# ESP32_SimButtonBox_Controller.net
KiCad netlist of a schematic drawn in EAGLE
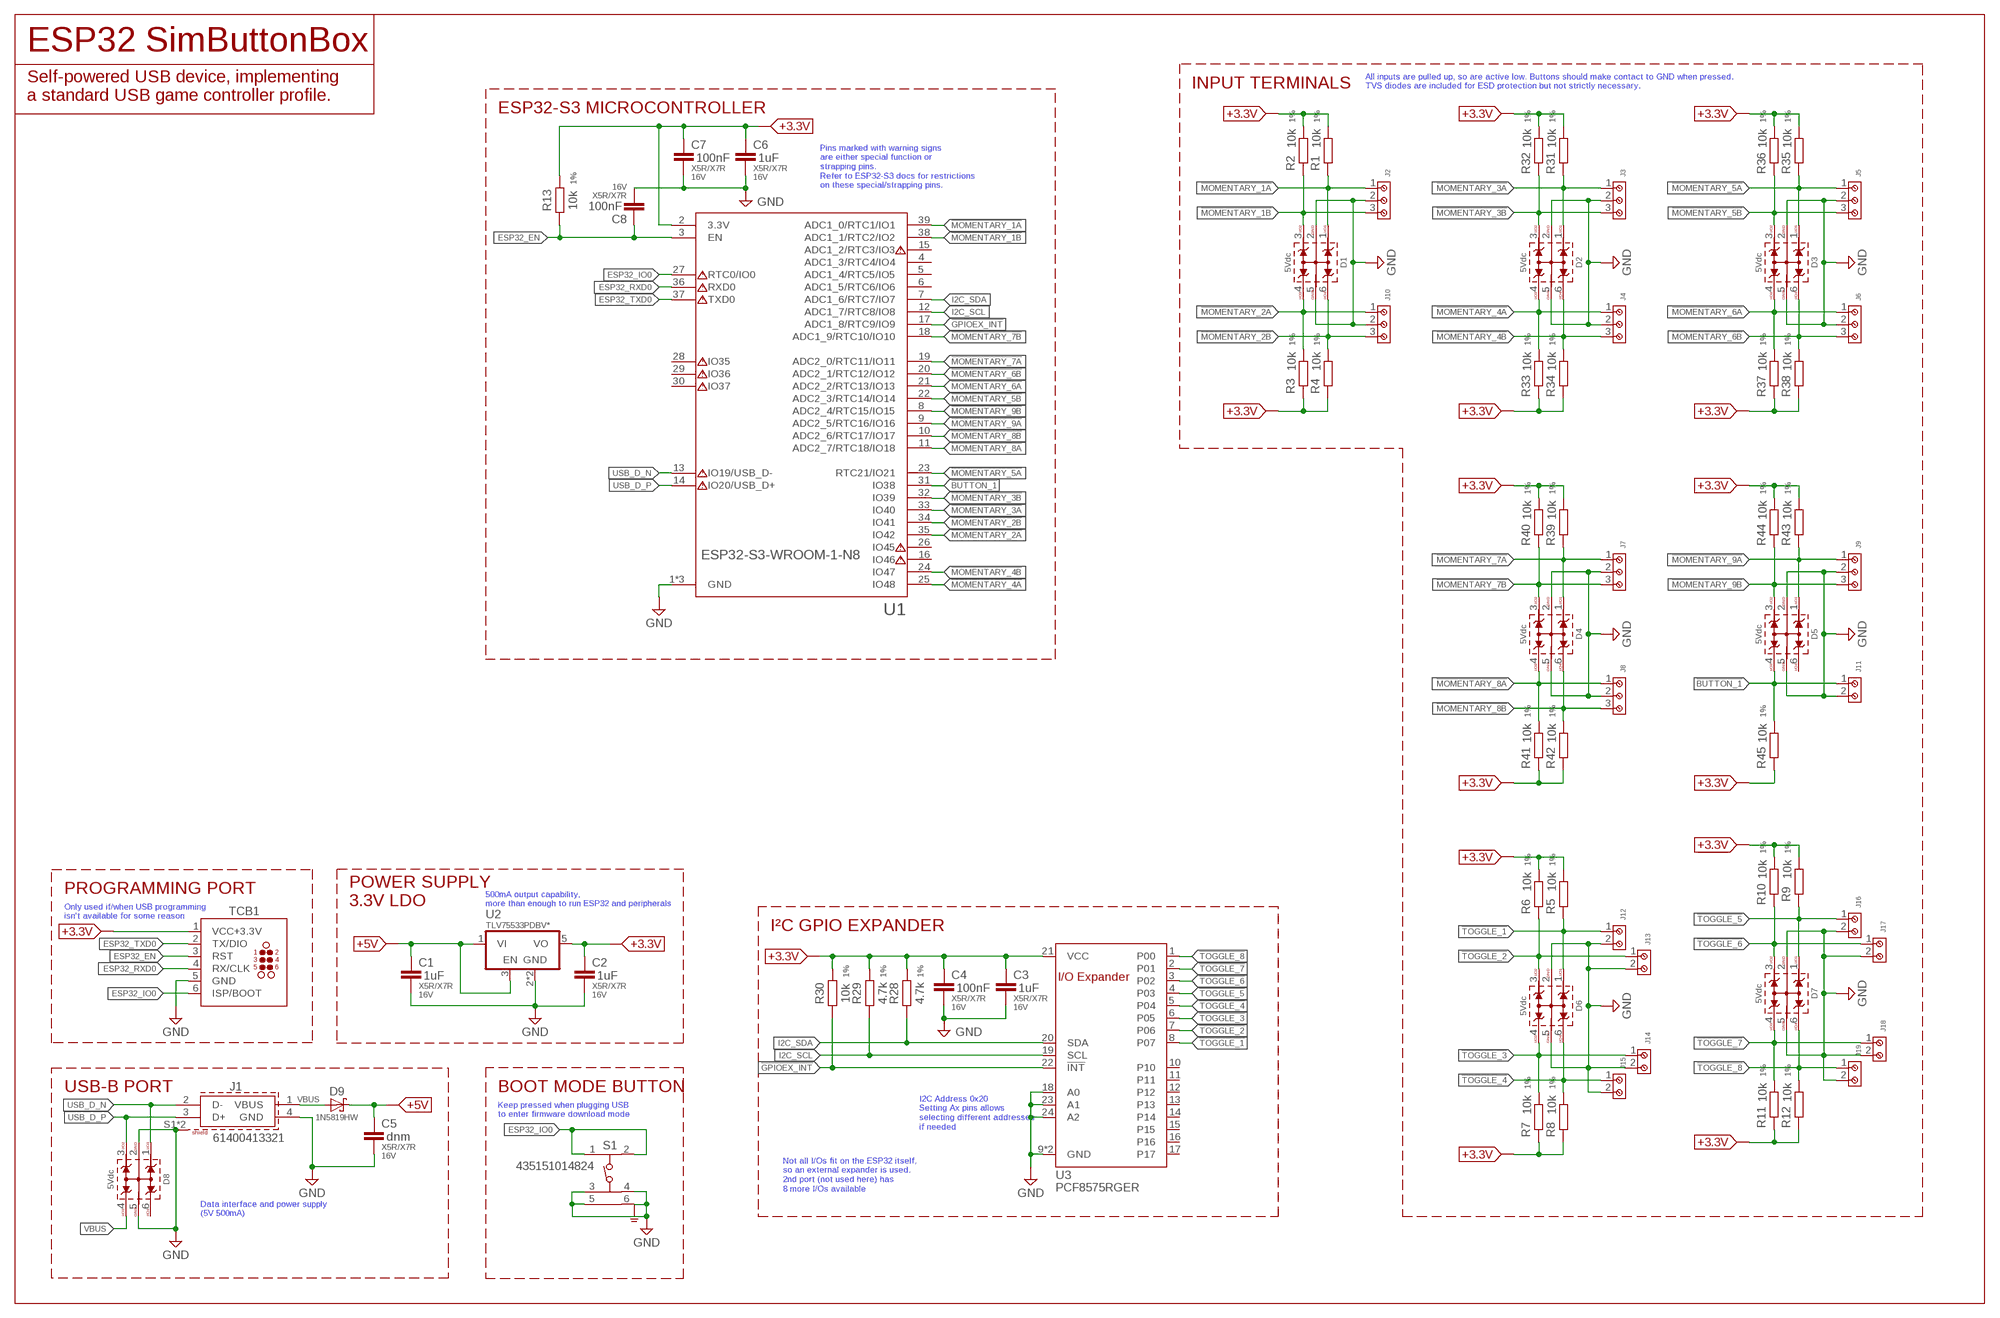
[diagram p0: schematic, sheet 1]

(export (version "E")
  (design (tool "Eeschema 10.0.6"))
  (components
    (comp (ref "C1")
      (value "1uF")
      (footprint "eagle-import:C0603")
      (fields (field (name "MATERIAL") "X5R/X7R") (field (name "VOLTAGE") "16V"))
      (libsource (lib "eagle-import") (part "CAP_0603"))
    )
    (comp (ref "C2")
      (value "1uF")
      (footprint "eagle-import:C0603")
      (fields (field (name "MATERIAL") "X5R/X7R") (field (name "VOLTAGE") "16V"))
      (libsource (lib "eagle-import") (part "CAP_0603"))
    )
    (comp (ref "C3")
      (value "1uF")
      (footprint "eagle-import:C0603")
      (fields (field (name "MATERIAL") "X5R/X7R") (field (name "VOLTAGE") "16V"))
      (libsource (lib "eagle-import") (part "CAP_0603"))
    )
    (comp (ref "C4")
      (value "100nF")
      (footprint "eagle-import:C0603")
      (fields (field (name "MATERIAL") "X5R/X7R") (field (name "VOLTAGE") "16V"))
      (libsource (lib "eagle-import") (part "CAP_0603"))
    )
    (comp (ref "C5")
      (value "dnm")
      (footprint "eagle-import:C0603")
      (fields (field (name "MATERIAL") "X5R/X7R") (field (name "VOLTAGE") "16V"))
      (libsource (lib "eagle-import") (part "CAP_0603"))
    )
    (comp (ref "C6")
      (value "1uF")
      (footprint "eagle-import:C0603")
      (fields (field (name "MATERIAL") "X5R/X7R") (field (name "VOLTAGE") "16V"))
      (libsource (lib "eagle-import") (part "CAP_0603"))
    )
    (comp (ref "C7")
      (value "100nF")
      (footprint "eagle-import:C0603")
      (fields (field (name "MATERIAL") "X5R/X7R") (field (name "VOLTAGE") "16V"))
      (libsource (lib "eagle-import") (part "CAP_0603"))
    )
    (comp (ref "C8")
      (value "100nF")
      (footprint "eagle-import:C0603")
      (fields (field (name "MATERIAL") "X5R/X7R") (field (name "VOLTAGE") "16V"))
      (libsource (lib "eagle-import") (part "CAP_0603"))
    )
    (comp (ref "D1")
      (value "5Vdc")
      (footprint "eagle-import:WE-TVS_SOT23-6L")
      (fields (field (name "MF") "Wurth Elektronik") (field (name "MP") "82402304"))
      (libsource (lib "eagle-import") (part "WE-TVS_SOT23-6L_82402304"))
    )
    (comp (ref "D2")
      (value "5Vdc")
      (footprint "eagle-import:WE-TVS_SOT23-6L")
      (fields (field (name "MF") "Wurth Elektronik") (field (name "MP") "82402304"))
      (libsource (lib "eagle-import") (part "WE-TVS_SOT23-6L_82402304"))
    )
    (comp (ref "D3")
      (value "5Vdc")
      (footprint "eagle-import:WE-TVS_SOT23-6L")
      (fields (field (name "MF") "Wurth Elektronik") (field (name "MP") "82402304"))
      (libsource (lib "eagle-import") (part "WE-TVS_SOT23-6L_82402304"))
    )
    (comp (ref "D4")
      (value "5Vdc")
      (footprint "eagle-import:WE-TVS_SOT23-6L")
      (fields (field (name "MF") "Wurth Elektronik") (field (name "MP") "82402304"))
      (libsource (lib "eagle-import") (part "WE-TVS_SOT23-6L_82402304"))
    )
    (comp (ref "D5")
      (value "5Vdc")
      (footprint "eagle-import:WE-TVS_SOT23-6L")
      (fields (field (name "MF") "Wurth Elektronik") (field (name "MP") "82402304"))
      (libsource (lib "eagle-import") (part "WE-TVS_SOT23-6L_82402304"))
    )
    (comp (ref "D6")
      (value "5Vdc")
      (footprint "eagle-import:WE-TVS_SOT23-6L")
      (fields (field (name "MF") "Wurth Elektronik") (field (name "MP") "82402304"))
      (libsource (lib "eagle-import") (part "WE-TVS_SOT23-6L_82402304"))
    )
    (comp (ref "D7")
      (value "5Vdc")
      (footprint "eagle-import:WE-TVS_SOT23-6L")
      (fields (field (name "MF") "Wurth Elektronik") (field (name "MP") "82402304"))
      (libsource (lib "eagle-import") (part "WE-TVS_SOT23-6L_82402304"))
    )
    (comp (ref "D8")
      (value "5Vdc")
      (footprint "eagle-import:WE-TVS_SOT23-6L")
      (fields (field (name "MF") "Wurth Elektronik") (field (name "MP") "82402304"))
      (libsource (lib "eagle-import") (part "WE-TVS_SOT23-6L_82402304"))
    )
    (comp (ref "D9")
      (value "1N5819HW")
      (footprint "eagle-import:SOD123")
      (fields (field (name "CURRENT") "1A") (field (name "MP") "1N5819HW"))
      (libsource (lib "eagle-import") (part "SCHOTTKY_SOD123"))
    )
    (comp (ref "J1")
      (value "61400413321")
      (footprint "eagle-import:61400413321")
      (fields (field (name "MF") "Wurth Elktronik"))
      (libsource (lib "eagle-import") (part "61400413321"))
    )
    (comp (ref "J2")
      (value "691210910003")
      (footprint "eagle-import:691210910003")
      (fields (field (name "MF") "Wurth Elektronik") (field (name "MP") " 691210910003 "))
      (libsource (lib "eagle-import") (part "691210910003"))
    )
    (comp (ref "J3")
      (value "691210910003")
      (footprint "eagle-import:691210910003")
      (fields (field (name "MF") "Wurth Elektronik") (field (name "MP") " 691210910003 "))
      (libsource (lib "eagle-import") (part "691210910003"))
    )
    (comp (ref "J4")
      (value "691210910003")
      (footprint "eagle-import:691210910003")
      (fields (field (name "MF") "Wurth Elektronik") (field (name "MP") " 691210910003 "))
      (libsource (lib "eagle-import") (part "691210910003"))
    )
    (comp (ref "J5")
      (value "691210910003")
      (footprint "eagle-import:691210910003")
      (fields (field (name "MF") "Wurth Elektronik") (field (name "MP") " 691210910003 "))
      (libsource (lib "eagle-import") (part "691210910003"))
    )
    (comp (ref "J6")
      (value "691210910003")
      (footprint "eagle-import:691210910003")
      (fields (field (name "MF") "Wurth Elektronik") (field (name "MP") " 691210910003 "))
      (libsource (lib "eagle-import") (part "691210910003"))
    )
    (comp (ref "J7")
      (value "691210910003")
      (footprint "eagle-import:691210910003")
      (fields (field (name "MF") "Wurth Elektronik") (field (name "MP") " 691210910003 "))
      (libsource (lib "eagle-import") (part "691210910003"))
    )
    (comp (ref "J8")
      (value "691210910003")
      (footprint "eagle-import:691210910003")
      (fields (field (name "MF") "Wurth Elektronik") (field (name "MP") " 691210910003 "))
      (libsource (lib "eagle-import") (part "691210910003"))
    )
    (comp (ref "J9")
      (value "691210910003")
      (footprint "eagle-import:691210910003")
      (fields (field (name "MF") "Wurth Elektronik") (field (name "MP") " 691210910003 "))
      (libsource (lib "eagle-import") (part "691210910003"))
    )
    (comp (ref "J10")
      (value "691210910003")
      (footprint "eagle-import:691210910003")
      (fields (field (name "MF") "Wurth Elektronik") (field (name "MP") " 691210910003 "))
      (libsource (lib "eagle-import") (part "691210910003"))
    )
    (comp (ref "J11")
      (value "691210910002")
      (footprint "eagle-import:691210910002")
      (fields (field (name "MF") "Wurth Elektronik") (field (name "MP") " 691210910002 "))
      (libsource (lib "eagle-import") (part "691210910002"))
    )
    (comp (ref "J12")
      (value "691210910002")
      (footprint "eagle-import:691210910002")
      (fields (field (name "MF") "Wurth Elektronik") (field (name "MP") " 691210910002 "))
      (libsource (lib "eagle-import") (part "691210910002"))
    )
    (comp (ref "J13")
      (value "691210910002")
      (footprint "eagle-import:691210910002")
      (fields (field (name "MF") "Wurth Elektronik") (field (name "MP") " 691210910002 "))
      (libsource (lib "eagle-import") (part "691210910002"))
    )
    (comp (ref "J14")
      (value "691210910002")
      (footprint "eagle-import:691210910002")
      (fields (field (name "MF") "Wurth Elektronik") (field (name "MP") " 691210910002 "))
      (libsource (lib "eagle-import") (part "691210910002"))
    )
    (comp (ref "J15")
      (value "691210910002")
      (footprint "eagle-import:691210910002")
      (fields (field (name "MF") "Wurth Elektronik") (field (name "MP") " 691210910002 "))
      (libsource (lib "eagle-import") (part "691210910002"))
    )
    (comp (ref "J16")
      (value "691210910002")
      (footprint "eagle-import:691210910002")
      (fields (field (name "MF") "Wurth Elektronik") (field (name "MP") " 691210910002 "))
      (libsource (lib "eagle-import") (part "691210910002"))
    )
    (comp (ref "J17")
      (value "691210910002")
      (footprint "eagle-import:691210910002")
      (fields (field (name "MF") "Wurth Elektronik") (field (name "MP") " 691210910002 "))
      (libsource (lib "eagle-import") (part "691210910002"))
    )
    (comp (ref "J18")
      (value "691210910002")
      (footprint "eagle-import:691210910002")
      (fields (field (name "MF") "Wurth Elektronik") (field (name "MP") " 691210910002 "))
      (libsource (lib "eagle-import") (part "691210910002"))
    )
    (comp (ref "J19")
      (value "691210910002")
      (footprint "eagle-import:691210910002")
      (fields (field (name "MF") "Wurth Elektronik") (field (name "MP") " 691210910002 "))
      (libsource (lib "eagle-import") (part "691210910002"))
    )
    (comp (ref "R1")
      (value "10k")
      (footprint "eagle-import:R0603")
      (fields (field (name "TOLERANCE") "1%"))
      (libsource (lib "eagle-import") (part "RES_0603"))
    )
    (comp (ref "R2")
      (value "10k")
      (footprint "eagle-import:R0603")
      (fields (field (name "TOLERANCE") "1%"))
      (libsource (lib "eagle-import") (part "RES_0603"))
    )
    (comp (ref "R3")
      (value "10k")
      (footprint "eagle-import:R0603")
      (fields (field (name "TOLERANCE") "1%"))
      (libsource (lib "eagle-import") (part "RES_0603"))
    )
    (comp (ref "R4")
      (value "10k")
      (footprint "eagle-import:R0603")
      (fields (field (name "TOLERANCE") "1%"))
      (libsource (lib "eagle-import") (part "RES_0603"))
    )
    (comp (ref "R5")
      (value "10k")
      (footprint "eagle-import:R0603")
      (fields (field (name "TOLERANCE") "1%"))
      (libsource (lib "eagle-import") (part "RES_0603"))
    )
    (comp (ref "R6")
      (value "10k")
      (footprint "eagle-import:R0603")
      (fields (field (name "TOLERANCE") "1%"))
      (libsource (lib "eagle-import") (part "RES_0603"))
    )
    (comp (ref "R7")
      (value "10k")
      (footprint "eagle-import:R0603")
      (fields (field (name "TOLERANCE") "1%"))
      (libsource (lib "eagle-import") (part "RES_0603"))
    )
    (comp (ref "R8")
      (value "10k")
      (footprint "eagle-import:R0603")
      (fields (field (name "TOLERANCE") "1%"))
      (libsource (lib "eagle-import") (part "RES_0603"))
    )
    (comp (ref "R9")
      (value "10k")
      (footprint "eagle-import:R0603")
      (fields (field (name "TOLERANCE") "1%"))
      (libsource (lib "eagle-import") (part "RES_0603"))
    )
    (comp (ref "R10")
      (value "10k")
      (footprint "eagle-import:R0603")
      (fields (field (name "TOLERANCE") "1%"))
      (libsource (lib "eagle-import") (part "RES_0603"))
    )
    (comp (ref "R11")
      (value "10k")
      (footprint "eagle-import:R0603")
      (fields (field (name "TOLERANCE") "1%"))
      (libsource (lib "eagle-import") (part "RES_0603"))
    )
    (comp (ref "R12")
      (value "10k")
      (footprint "eagle-import:R0603")
      (fields (field (name "TOLERANCE") "1%"))
      (libsource (lib "eagle-import") (part "RES_0603"))
    )
    (comp (ref "R13")
      (value "10k")
      (footprint "eagle-import:R0603")
      (fields (field (name "TOLERANCE") "1%"))
      (libsource (lib "eagle-import") (part "RES_0603"))
    )
    (comp (ref "R28")
      (value "4.7k")
      (footprint "eagle-import:R0603")
      (fields (field (name "TOLERANCE") "1%"))
      (libsource (lib "eagle-import") (part "RES_0603"))
    )
    (comp (ref "R29")
      (value "4.7k")
      (footprint "eagle-import:R0603")
      (fields (field (name "TOLERANCE") "1%"))
      (libsource (lib "eagle-import") (part "RES_0603"))
    )
    (comp (ref "R30")
      (value "10k")
      (footprint "eagle-import:R0603")
      (fields (field (name "TOLERANCE") "1%"))
      (libsource (lib "eagle-import") (part "RES_0603"))
    )
    (comp (ref "R31")
      (value "10k")
      (footprint "eagle-import:R0603")
      (fields (field (name "TOLERANCE") "1%"))
      (libsource (lib "eagle-import") (part "RES_0603"))
    )
    (comp (ref "R32")
      (value "10k")
      (footprint "eagle-import:R0603")
      (fields (field (name "TOLERANCE") "1%"))
      (libsource (lib "eagle-import") (part "RES_0603"))
    )
    (comp (ref "R33")
      (value "10k")
      (footprint "eagle-import:R0603")
      (fields (field (name "TOLERANCE") "1%"))
      (libsource (lib "eagle-import") (part "RES_0603"))
    )
    (comp (ref "R34")
      (value "10k")
      (footprint "eagle-import:R0603")
      (fields (field (name "TOLERANCE") "1%"))
      (libsource (lib "eagle-import") (part "RES_0603"))
    )
    (comp (ref "R35")
      (value "10k")
      (footprint "eagle-import:R0603")
      (fields (field (name "TOLERANCE") "1%"))
      (libsource (lib "eagle-import") (part "RES_0603"))
    )
    (comp (ref "R36")
      (value "10k")
      (footprint "eagle-import:R0603")
      (fields (field (name "TOLERANCE") "1%"))
      (libsource (lib "eagle-import") (part "RES_0603"))
    )
    (comp (ref "R37")
      (value "10k")
      (footprint "eagle-import:R0603")
      (fields (field (name "TOLERANCE") "1%"))
      (libsource (lib "eagle-import") (part "RES_0603"))
    )
    (comp (ref "R38")
      (value "10k")
      (footprint "eagle-import:R0603")
      (fields (field (name "TOLERANCE") "1%"))
      (libsource (lib "eagle-import") (part "RES_0603"))
    )
    (comp (ref "R39")
      (value "10k")
      (footprint "eagle-import:R0603")
      (fields (field (name "TOLERANCE") "1%"))
      (libsource (lib "eagle-import") (part "RES_0603"))
    )
    (comp (ref "R40")
      (value "10k")
      (footprint "eagle-import:R0603")
      (fields (field (name "TOLERANCE") "1%"))
      (libsource (lib "eagle-import") (part "RES_0603"))
    )
    (comp (ref "R41")
      (value "10k")
      (footprint "eagle-import:R0603")
      (fields (field (name "TOLERANCE") "1%"))
      (libsource (lib "eagle-import") (part "RES_0603"))
    )
    (comp (ref "R42")
      (value "10k")
      (footprint "eagle-import:R0603")
      (fields (field (name "TOLERANCE") "1%"))
      (libsource (lib "eagle-import") (part "RES_0603"))
    )
    (comp (ref "R43")
      (value "10k")
      (footprint "eagle-import:R0603")
      (fields (field (name "TOLERANCE") "1%"))
      (libsource (lib "eagle-import") (part "RES_0603"))
    )
    (comp (ref "R44")
      (value "10k")
      (footprint "eagle-import:R0603")
      (fields (field (name "TOLERANCE") "1%"))
      (libsource (lib "eagle-import") (part "RES_0603"))
    )
    (comp (ref "R45")
      (value "10k")
      (footprint "eagle-import:R0603")
      (fields (field (name "TOLERANCE") "1%"))
      (libsource (lib "eagle-import") (part "RES_0603"))
    )
    (comp (ref "S1")
      (value "435151014824")
      (footprint "eagle-import:435151014824")
      (fields (field (name "MF") "Wurth Elektronik") (field (name "MP") "435151014824 "))
      (libsource (lib "eagle-import") (part "435151014824"))
    )
    (comp (ref "TCB1")
      (value "TC2030-MCP-NL")
      (footprint "eagle-import:TC2030-MCP-NL")
      (libsource (lib "eagle-import") (part "TC2030-MCP-NL"))
    )
    (comp (ref "U1")
      (value "ESP32-S3-WROOM-1-N8")
      (footprint "eagle-import:WROOM-1")
      (fields (field (name "MF") "Espressif Systems") (field (name "MP") "ESP32-S3-WROOM-1-N8"))
      (libsource (lib "eagle-import") (part "ESP32-S3-WROOM-1-N8"))
    )
    (comp (ref "U2")
      (value "LDO_EN_SOT23-5")
      (footprint "eagle-import:SOT23-5")
      (fields
        (field (name "IOUT") "500mA")
        (field (name "MF") "Texas Instruments")
        (field (name "MP") "TLV75533PDBV*")
        (field (name "VMAX") "5.5V")
        (field (name "VMIN") "1.45V")
      )
      (libsource (lib "eagle-import") (part "LDO_EN_SOT23-5"))
    )
    (comp (ref "U3")
      (value "PCF8575RGE")
      (footprint "eagle-import:QFN50P400X400X100-25T210N")
      (fields (field (name "MP") "PCF8575RGER") (field (name "MF") "Texas Instruments"))
      (libsource (lib "eagle-import") (part "PCF8575RGE"))
    )
  )
  (nets
    (net (code "1") (name "+3.3V") (class "Default")
      (node (ref "C2") (pin "1") (pinfunction "1_1") (pintype "passive"))
      (node (ref "C3") (pin "1") (pinfunction "1_1") (pintype "passive"))
      (node (ref "C4") (pin "1") (pinfunction "1_1") (pintype "passive"))
      (node (ref "C6") (pin "1") (pinfunction "1_1") (pintype "passive"))
      (node (ref "C7") (pin "1") (pinfunction "1_1") (pintype "passive"))
      (node (ref "R1") (pin "2") (pinfunction "2_2") (pintype "passive"))
      (node (ref "R10") (pin "2") (pinfunction "2_2") (pintype "passive"))
      (node (ref "R11") (pin "1") (pinfunction "1_1") (pintype "passive"))
      (node (ref "R12") (pin "1") (pinfunction "1_1") (pintype "passive"))
      (node (ref "R13") (pin "2") (pinfunction "2_2") (pintype "passive"))
      (node (ref "R2") (pin "2") (pinfunction "2_2") (pintype "passive"))
      (node (ref "R28") (pin "2") (pinfunction "2_2") (pintype "passive"))
      (node (ref "R29") (pin "2") (pinfunction "2_2") (pintype "passive"))
      (node (ref "R3") (pin "1") (pinfunction "1_1") (pintype "passive"))
      (node (ref "R30") (pin "2") (pinfunction "2_2") (pintype "passive"))
      (node (ref "R31") (pin "2") (pinfunction "2_2") (pintype "passive"))
      (node (ref "R32") (pin "2") (pinfunction "2_2") (pintype "passive"))
      (node (ref "R33") (pin "1") (pinfunction "1_1") (pintype "passive"))
      (node (ref "R34") (pin "1") (pinfunction "1_1") (pintype "passive"))
      (node (ref "R35") (pin "2") (pinfunction "2_2") (pintype "passive"))
      (node (ref "R36") (pin "2") (pinfunction "2_2") (pintype "passive"))
      (node (ref "R37") (pin "1") (pinfunction "1_1") (pintype "passive"))
      (node (ref "R38") (pin "1") (pinfunction "1_1") (pintype "passive"))
      (node (ref "R39") (pin "2") (pinfunction "2_2") (pintype "passive"))
      (node (ref "R4") (pin "1") (pinfunction "1_1") (pintype "passive"))
      (node (ref "R40") (pin "2") (pinfunction "2_2") (pintype "passive"))
      (node (ref "R41") (pin "1") (pinfunction "1_1") (pintype "passive"))
      (node (ref "R42") (pin "1") (pinfunction "1_1") (pintype "passive"))
      (node (ref "R43") (pin "2") (pinfunction "2_2") (pintype "passive"))
      (node (ref "R44") (pin "2") (pinfunction "2_2") (pintype "passive"))
      (node (ref "R45") (pin "1") (pinfunction "1_1") (pintype "passive"))
      (node (ref "R5") (pin "2") (pinfunction "2_2") (pintype "passive"))
      (node (ref "R6") (pin "2") (pinfunction "2_2") (pintype "passive"))
      (node (ref "R7") (pin "1") (pinfunction "1_1") (pintype "passive"))
      (node (ref "R8") (pin "1") (pinfunction "1_1") (pintype "passive"))
      (node (ref "R9") (pin "2") (pinfunction "2_2") (pintype "passive"))
      (node (ref "TCB1") (pin "1") (pinfunction "VCC+3.3V_1") (pintype "bidirectional"))
      (node (ref "U1") (pin "2") (pinfunction "3.3V_2") (pintype "passive"))
      (node (ref "U2") (pin "5") (pinfunction "VO_5") (pintype "passive"))
      (node (ref "U3") (pin "21") (pinfunction "VCC_21") (pintype "bidirectional"))
    )
    (net (code "2") (name "+5V") (class "Default")
      (node (ref "C1") (pin "1") (pinfunction "1_1") (pintype "passive"))
      (node (ref "C5") (pin "1") (pinfunction "1_1") (pintype "passive"))
      (node (ref "D9") (pin "C") (pinfunction "C_C") (pintype "passive"))
      (node (ref "U2") (pin "1") (pinfunction "VI_1") (pintype "input"))
      (node (ref "U2") (pin "3") (pinfunction "EN_3") (pintype "input"))
    )
    (net (code "3") (name "/~{BUTTON_1}") (class "Default")
      (node (ref "D5") (pin "4") (pinfunction "3_4") (pintype "passive"))
      (node (ref "J11") (pin "1") (pinfunction "1_1") (pintype "passive"))
      (node (ref "R45") (pin "2") (pinfunction "2_2") (pintype "passive"))
      (node (ref "U1") (pin "31") (pinfunction "IO38_31") (pintype "bidirectional"))
    )
    (net (code "4") (name "/~{GPIOEX_INT}") (class "Default")
      (node (ref "R30") (pin "1") (pinfunction "1_1") (pintype "passive"))
      (node (ref "U1") (pin "17") (pinfunction "ADC1_8/RTC9/IO9_17") (pintype "bidirectional"))
      (node (ref "U3") (pin "22") (pinfunction "~{INT}_22") (pintype "bidirectional"))
    )
    (net (code "5") (name "/~{MOMENTARY_1A}") (class "Default")
      (node (ref "D1") (pin "1") (pinfunction "1_1") (pintype "passive"))
      (node (ref "J2") (pin "1") (pinfunction "1_1") (pintype "passive"))
      (node (ref "R1") (pin "1") (pinfunction "1_1") (pintype "passive"))
      (node (ref "U1") (pin "39") (pinfunction "ADC1_0/RTC1/IO1_39") (pintype "bidirectional"))
    )
    (net (code "6") (name "/~{MOMENTARY_1B}") (class "Default")
      (node (ref "D1") (pin "3") (pinfunction "2_3") (pintype "passive"))
      (node (ref "J2") (pin "3") (pinfunction "3_3") (pintype "passive"))
      (node (ref "R2") (pin "1") (pinfunction "1_1") (pintype "passive"))
      (node (ref "U1") (pin "38") (pinfunction "ADC1_1/RTC2/IO2_38") (pintype "bidirectional"))
    )
    (net (code "7") (name "/~{MOMENTARY_2A}") (class "Default")
      (node (ref "D1") (pin "4") (pinfunction "3_4") (pintype "passive"))
      (node (ref "J10") (pin "1") (pinfunction "1_1") (pintype "passive"))
      (node (ref "R3") (pin "2") (pinfunction "2_2") (pintype "passive"))
      (node (ref "U1") (pin "35") (pinfunction "IO42_35") (pintype "bidirectional"))
    )
    (net (code "8") (name "/~{MOMENTARY_2B}") (class "Default")
      (node (ref "D1") (pin "6") (pinfunction "4_6") (pintype "passive"))
      (node (ref "J10") (pin "3") (pinfunction "3_3") (pintype "passive"))
      (node (ref "R4") (pin "2") (pinfunction "2_2") (pintype "passive"))
      (node (ref "U1") (pin "34") (pinfunction "IO41_34") (pintype "bidirectional"))
    )
    (net (code "9") (name "/~{MOMENTARY_3A}") (class "Default")
      (node (ref "D2") (pin "1") (pinfunction "1_1") (pintype "passive"))
      (node (ref "J3") (pin "1") (pinfunction "1_1") (pintype "passive"))
      (node (ref "R31") (pin "1") (pinfunction "1_1") (pintype "passive"))
      (node (ref "U1") (pin "33") (pinfunction "IO40_33") (pintype "bidirectional"))
    )
    (net (code "10") (name "/~{MOMENTARY_3B}") (class "Default")
      (node (ref "D2") (pin "3") (pinfunction "2_3") (pintype "passive"))
      (node (ref "J3") (pin "3") (pinfunction "3_3") (pintype "passive"))
      (node (ref "R32") (pin "1") (pinfunction "1_1") (pintype "passive"))
      (node (ref "U1") (pin "32") (pinfunction "IO39_32") (pintype "bidirectional"))
    )
    (net (code "11") (name "/~{MOMENTARY_4A}") (class "Default")
      (node (ref "D2") (pin "4") (pinfunction "3_4") (pintype "passive"))
      (node (ref "J4") (pin "1") (pinfunction "1_1") (pintype "passive"))
      (node (ref "R33") (pin "2") (pinfunction "2_2") (pintype "passive"))
      (node (ref "U1") (pin "25") (pinfunction "IO48_25") (pintype "bidirectional"))
    )
    (net (code "12") (name "/~{MOMENTARY_4B}") (class "Default")
      (node (ref "D2") (pin "6") (pinfunction "4_6") (pintype "passive"))
      (node (ref "J4") (pin "3") (pinfunction "3_3") (pintype "passive"))
      (node (ref "R34") (pin "2") (pinfunction "2_2") (pintype "passive"))
      (node (ref "U1") (pin "24") (pinfunction "IO47_24") (pintype "bidirectional"))
    )
    (net (code "13") (name "/~{MOMENTARY_5A}") (class "Default")
      (node (ref "D3") (pin "1") (pinfunction "1_1") (pintype "passive"))
      (node (ref "J5") (pin "1") (pinfunction "1_1") (pintype "passive"))
      (node (ref "R35") (pin "1") (pinfunction "1_1") (pintype "passive"))
      (node (ref "U1") (pin "23") (pinfunction "RTC21/IO21_23") (pintype "bidirectional"))
    )
    (net (code "14") (name "/~{MOMENTARY_5B}") (class "Default")
      (node (ref "D3") (pin "3") (pinfunction "2_3") (pintype "passive"))
      (node (ref "J5") (pin "3") (pinfunction "3_3") (pintype "passive"))
      (node (ref "R36") (pin "1") (pinfunction "1_1") (pintype "passive"))
      (node (ref "U1") (pin "22") (pinfunction "ADC2_3/RTC14/IO14_22") (pintype "bidirectional"))
    )
    (net (code "15") (name "/~{MOMENTARY_6A}") (class "Default")
      (node (ref "D3") (pin "4") (pinfunction "3_4") (pintype "passive"))
      (node (ref "J6") (pin "1") (pinfunction "1_1") (pintype "passive"))
      (node (ref "R37") (pin "2") (pinfunction "2_2") (pintype "passive"))
      (node (ref "U1") (pin "21") (pinfunction "ADC2_2/RTC13/IO13_21") (pintype "bidirectional"))
    )
    (net (code "16") (name "/~{MOMENTARY_6B}") (class "Default")
      (node (ref "D3") (pin "6") (pinfunction "4_6") (pintype "passive"))
      (node (ref "J6") (pin "3") (pinfunction "3_3") (pintype "passive"))
      (node (ref "R38") (pin "2") (pinfunction "2_2") (pintype "passive"))
      (node (ref "U1") (pin "20") (pinfunction "ADC2_1/RTC12/IO12_20") (pintype "bidirectional"))
    )
    (net (code "17") (name "/~{MOMENTARY_7A}") (class "Default")
      (node (ref "D4") (pin "1") (pinfunction "1_1") (pintype "passive"))
      (node (ref "J7") (pin "1") (pinfunction "1_1") (pintype "passive"))
      (node (ref "R39") (pin "1") (pinfunction "1_1") (pintype "passive"))
      (node (ref "U1") (pin "19") (pinfunction "ADC2_0/RTC11/IO11_19") (pintype "bidirectional"))
    )
    (net (code "18") (name "/~{MOMENTARY_7B}") (class "Default")
      (node (ref "D4") (pin "3") (pinfunction "2_3") (pintype "passive"))
      (node (ref "J7") (pin "3") (pinfunction "3_3") (pintype "passive"))
      (node (ref "R40") (pin "1") (pinfunction "1_1") (pintype "passive"))
      (node (ref "U1") (pin "18") (pinfunction "ADC1_9/RTC10/IO10_18") (pintype "bidirectional"))
    )
    (net (code "19") (name "/~{MOMENTARY_8A}") (class "Default")
      (node (ref "D4") (pin "4") (pinfunction "3_4") (pintype "passive"))
      (node (ref "J8") (pin "1") (pinfunction "1_1") (pintype "passive"))
      (node (ref "R41") (pin "2") (pinfunction "2_2") (pintype "passive"))
      (node (ref "U1") (pin "11") (pinfunction "ADC2_7/RTC18/IO18_11") (pintype "bidirectional"))
    )
    (net (code "20") (name "/~{MOMENTARY_8B}") (class "Default")
      (node (ref "D4") (pin "6") (pinfunction "4_6") (pintype "passive"))
      (node (ref "J8") (pin "3") (pinfunction "3_3") (pintype "passive"))
      (node (ref "R42") (pin "2") (pinfunction "2_2") (pintype "passive"))
      (node (ref "U1") (pin "10") (pinfunction "ADC2_6/RTC17/IO17_10") (pintype "bidirectional"))
    )
    (net (code "21") (name "/~{MOMENTARY_9A}") (class "Default")
      (node (ref "D5") (pin "1") (pinfunction "1_1") (pintype "passive"))
      (node (ref "J9") (pin "1") (pinfunction "1_1") (pintype "passive"))
      (node (ref "R43") (pin "1") (pinfunction "1_1") (pintype "passive"))
      (node (ref "U1") (pin "9") (pinfunction "ADC2_5/RTC16/IO16_9") (pintype "bidirectional"))
    )
    (net (code "22") (name "/~{MOMENTARY_9B}") (class "Default")
      (node (ref "D5") (pin "3") (pinfunction "2_3") (pintype "passive"))
      (node (ref "J9") (pin "3") (pinfunction "3_3") (pintype "passive"))
      (node (ref "R44") (pin "1") (pinfunction "1_1") (pintype "passive"))
      (node (ref "U1") (pin "8") (pinfunction "ADC2_4/RTC15/IO15_8") (pintype "bidirectional"))
    )
    (net (code "23") (name "/~{TOGGLE_1}") (class "Default")
      (node (ref "D6") (pin "1") (pinfunction "1_1") (pintype "passive"))
      (node (ref "J12") (pin "1") (pinfunction "1_1") (pintype "passive"))
      (node (ref "R5") (pin "1") (pinfunction "1_1") (pintype "passive"))
      (node (ref "U3") (pin "8") (pinfunction "P07_8") (pintype "bidirectional"))
    )
    (net (code "24") (name "/~{TOGGLE_2}") (class "Default")
      (node (ref "D6") (pin "3") (pinfunction "2_3") (pintype "passive"))
      (node (ref "J13") (pin "1") (pinfunction "1_1") (pintype "passive"))
      (node (ref "R6") (pin "1") (pinfunction "1_1") (pintype "passive"))
      (node (ref "U3") (pin "7") (pinfunction "P06_7") (pintype "bidirectional"))
    )
    (net (code "25") (name "/~{TOGGLE_3}") (class "Default")
      (node (ref "D6") (pin "4") (pinfunction "3_4") (pintype "passive"))
      (node (ref "J14") (pin "1") (pinfunction "1_1") (pintype "passive"))
      (node (ref "R7") (pin "2") (pinfunction "2_2") (pintype "passive"))
      (node (ref "U3") (pin "6") (pinfunction "P05_6") (pintype "bidirectional"))
    )
    (net (code "26") (name "/~{TOGGLE_4}") (class "Default")
      (node (ref "D6") (pin "6") (pinfunction "4_6") (pintype "passive"))
      (node (ref "J15") (pin "1") (pinfunction "1_1") (pintype "passive"))
      (node (ref "R8") (pin "2") (pinfunction "2_2") (pintype "passive"))
      (node (ref "U3") (pin "5") (pinfunction "P04_5") (pintype "bidirectional"))
    )
    (net (code "27") (name "/~{TOGGLE_5}") (class "Default")
      (node (ref "D7") (pin "1") (pinfunction "1_1") (pintype "passive"))
      (node (ref "J16") (pin "1") (pinfunction "1_1") (pintype "passive"))
      (node (ref "R9") (pin "1") (pinfunction "1_1") (pintype "passive"))
      (node (ref "U3") (pin "4") (pinfunction "P03_4") (pintype "bidirectional"))
    )
    (net (code "28") (name "/~{TOGGLE_6}") (class "Default")
      (node (ref "D7") (pin "3") (pinfunction "2_3") (pintype "passive"))
      (node (ref "J17") (pin "1") (pinfunction "1_1") (pintype "passive"))
      (node (ref "R10") (pin "1") (pinfunction "1_1") (pintype "passive"))
      (node (ref "U3") (pin "3") (pinfunction "P02_3") (pintype "bidirectional"))
    )
    (net (code "29") (name "/~{TOGGLE_7}") (class "Default")
      (node (ref "D7") (pin "4") (pinfunction "3_4") (pintype "passive"))
      (node (ref "J18") (pin "1") (pinfunction "1_1") (pintype "passive"))
      (node (ref "R11") (pin "2") (pinfunction "2_2") (pintype "passive"))
      (node (ref "U3") (pin "2") (pinfunction "P01_2") (pintype "bidirectional"))
    )
    (net (code "30") (name "/~{TOGGLE_8}") (class "Default")
      (node (ref "D7") (pin "6") (pinfunction "4_6") (pintype "passive"))
      (node (ref "J19") (pin "1") (pinfunction "1_1") (pintype "passive"))
      (node (ref "R12") (pin "2") (pinfunction "2_2") (pintype "passive"))
      (node (ref "U3") (pin "1") (pinfunction "P00_1") (pintype "bidirectional"))
    )
    (net (code "31") (name "ESP32_EN") (class "Default")
      (node (ref "C8") (pin "1") (pinfunction "1_1") (pintype "passive"))
      (node (ref "R13") (pin "1") (pinfunction "1_1") (pintype "passive"))
      (node (ref "TCB1") (pin "3") (pinfunction "RST_3") (pintype "bidirectional"))
      (node (ref "U1") (pin "3") (pinfunction "EN_3") (pintype "bidirectional"))
    )
    (net (code "32") (name "ESP32_IO0") (class "Default")
      (node (ref "S1") (pin "1") (pinfunction "1_1") (pintype "passive"))
      (node (ref "S1") (pin "2") (pinfunction "2_2") (pintype "passive"))
      (node (ref "TCB1") (pin "6") (pinfunction "ISP/BOOT_6") (pintype "bidirectional"))
      (node (ref "U1") (pin "27") (pinfunction "RTC0/IO0_27") (pintype "bidirectional"))
    )
    (net (code "33") (name "ESP32_RXD0") (class "Default")
      (node (ref "TCB1") (pin "4") (pinfunction "RX/CLK_4") (pintype "bidirectional"))
      (node (ref "U1") (pin "36") (pinfunction "RXD0_36") (pintype "bidirectional"))
    )
    (net (code "34") (name "ESP32_TXD0") (class "Default")
      (node (ref "TCB1") (pin "2") (pinfunction "TX/DIO_2") (pintype "bidirectional"))
      (node (ref "U1") (pin "37") (pinfunction "TXD0_37") (pintype "bidirectional"))
    )
    (net (code "35") (name "GND") (class "Default")
      (node (ref "C1") (pin "2") (pinfunction "2_2") (pintype "passive"))
      (node (ref "C2") (pin "2") (pinfunction "2_2") (pintype "passive"))
      (node (ref "C3") (pin "2") (pinfunction "2_2") (pintype "passive"))
      (node (ref "C4") (pin "2") (pinfunction "2_2") (pintype "passive"))
      (node (ref "C5") (pin "2") (pinfunction "2_2") (pintype "passive"))
      (node (ref "C6") (pin "2") (pinfunction "2_2") (pintype "passive"))
      (node (ref "C7") (pin "2") (pinfunction "2_2") (pintype "passive"))
      (node (ref "C8") (pin "2") (pinfunction "2_2") (pintype "passive"))
      (node (ref "D1") (pin "2") (pinfunction "GND_2") (pintype "passive"))
      (node (ref "D1") (pin "5") (pinfunction "GND_5") (pintype "passive"))
      (node (ref "D2") (pin "2") (pinfunction "GND_2") (pintype "passive"))
      (node (ref "D2") (pin "5") (pinfunction "GND_5") (pintype "passive"))
      (node (ref "D3") (pin "2") (pinfunction "GND_2") (pintype "passive"))
      (node (ref "D3") (pin "5") (pinfunction "GND_5") (pintype "passive"))
      (node (ref "D4") (pin "2") (pinfunction "GND_2") (pintype "passive"))
      (node (ref "D4") (pin "5") (pinfunction "GND_5") (pintype "passive"))
      (node (ref "D5") (pin "2") (pinfunction "GND_2") (pintype "passive"))
      (node (ref "D5") (pin "5") (pinfunction "GND_5") (pintype "passive"))
      (node (ref "D6") (pin "2") (pinfunction "GND_2") (pintype "passive"))
      (node (ref "D6") (pin "5") (pinfunction "GND_5") (pintype "passive"))
      (node (ref "D7") (pin "2") (pinfunction "GND_2") (pintype "passive"))
      (node (ref "D7") (pin "5") (pinfunction "GND_5") (pintype "passive"))
      (node (ref "D8") (pin "2") (pinfunction "GND_2") (pintype "passive"))
      (node (ref "D8") (pin "5") (pinfunction "GND_5") (pintype "passive"))
      (node (ref "J1") (pin "4") (pinfunction "GND_4") (pintype "passive"))
      (node (ref "J1") (pin "S1") (pinfunction "SHIELD_S1") (pintype "passive"))
      (node (ref "J1") (pin "S2") (pinfunction "SHIELD_S2") (pintype "passive"))
      (node (ref "J10") (pin "2") (pinfunction "2_2") (pintype "passive"))
      (node (ref "J11") (pin "2") (pinfunction "2_2") (pintype "passive"))
      (node (ref "J12") (pin "2") (pinfunction "2_2") (pintype "passive"))
      (node (ref "J13") (pin "2") (pinfunction "2_2") (pintype "passive"))
      (node (ref "J14") (pin "2") (pinfunction "2_2") (pintype "passive"))
      (node (ref "J15") (pin "2") (pinfunction "2_2") (pintype "passive"))
      (node (ref "J16") (pin "2") (pinfunction "2_2") (pintype "passive"))
      (node (ref "J17") (pin "2") (pinfunction "2_2") (pintype "passive"))
      (node (ref "J18") (pin "2") (pinfunction "2_2") (pintype "passive"))
      (node (ref "J19") (pin "2") (pinfunction "2_2") (pintype "passive"))
      (node (ref "J2") (pin "2") (pinfunction "2_2") (pintype "passive"))
      (node (ref "J3") (pin "2") (pinfunction "2_2") (pintype "passive"))
      (node (ref "J4") (pin "2") (pinfunction "2_2") (pintype "passive"))
      (node (ref "J5") (pin "2") (pinfunction "2_2") (pintype "passive"))
      (node (ref "J6") (pin "2") (pinfunction "2_2") (pintype "passive"))
      (node (ref "J7") (pin "2") (pinfunction "2_2") (pintype "passive"))
      (node (ref "J8") (pin "2") (pinfunction "2_2") (pintype "passive"))
      (node (ref "J9") (pin "2") (pinfunction "2_2") (pintype "passive"))
      (node (ref "S1") (pin "3") (pinfunction "3_3") (pintype "passive"))
      (node (ref "S1") (pin "4") (pinfunction "4_4") (pintype "passive"))
      (node (ref "S1") (pin "5") (pinfunction "5_5") (pintype "passive"))
      (node (ref "S1") (pin "6") (pinfunction "6_6") (pintype "passive"))
      (node (ref "TCB1") (pin "5") (pinfunction "GND_5") (pintype "bidirectional"))
      (node (ref "U1") (pin "1") (pinfunction "GND_1") (pintype "bidirectional"))
      (node (ref "U1") (pin "40") (pinfunction "GND_40") (pintype "bidirectional"))
      (node (ref "U1") (pin "P$1") (pinfunction "GND_P$1") (pintype "bidirectional"))
      (node (ref "U2") (pin "2") (pinfunction "GND_2") (pintype "input"))
      (node (ref "U2") (pin "4") (pinfunction "GND_4") (pintype "input"))
      (node (ref "U3") (pin "18") (pinfunction "A0_18") (pintype "bidirectional"))
      (node (ref "U3") (pin "23") (pinfunction "A1_23") (pintype "bidirectional"))
      (node (ref "U3") (pin "24") (pinfunction "A2_24") (pintype "bidirectional"))
      (node (ref "U3") (pin "25") (pinfunction "GND_25") (pintype "bidirectional"))
      (node (ref "U3") (pin "9") (pinfunction "GND_9") (pintype "bidirectional"))
    )
    (net (code "36") (name "I2C_SCL") (class "Default")
      (node (ref "R29") (pin "1") (pinfunction "1_1") (pintype "passive"))
      (node (ref "U1") (pin "12") (pinfunction "ADC1_7/RTC8/IO8_12") (pintype "bidirectional"))
      (node (ref "U3") (pin "19") (pinfunction "SCL_19") (pintype "bidirectional"))
    )
    (net (code "37") (name "I2C_SDA") (class "Default")
      (node (ref "R28") (pin "1") (pinfunction "1_1") (pintype "passive"))
      (node (ref "U1") (pin "7") (pinfunction "ADC1_6/RTC7/IO7_7") (pintype "bidirectional"))
      (node (ref "U3") (pin "20") (pinfunction "SDA_20") (pintype "bidirectional"))
    )
    (net (code "38") (name "USB_D_N") (class "Default")
      (node (ref "D8") (pin "1") (pinfunction "1_1") (pintype "passive"))
      (node (ref "J1") (pin "2") (pinfunction "D-_2") (pintype "passive"))
      (node (ref "U1") (pin "13") (pinfunction "IO19/USB_D-_13") (pintype "bidirectional"))
    )
    (net (code "39") (name "USB_D_P") (class "Default")
      (node (ref "D8") (pin "3") (pinfunction "2_3") (pintype "passive"))
      (node (ref "J1") (pin "3") (pinfunction "D+_3") (pintype "passive"))
      (node (ref "U1") (pin "14") (pinfunction "IO20/USB_D+_14") (pintype "bidirectional"))
    )
    (net (code "40") (name "VBUS") (class "Default")
      (node (ref "D8") (pin "4") (pinfunction "3_4") (pintype "passive"))
      (node (ref "D9") (pin "A") (pinfunction "A_A") (pintype "passive"))
      (node (ref "J1") (pin "1") (pinfunction "VBUS_1") (pintype "passive"))
    )
    (net (code "41") (name "unconnected-(D5-4-Pad6)") (class "Default")
      (node (ref "D5") (pin "6") (pinfunction "4_6") (pintype "passive"))
    )
    (net (code "42") (name "unconnected-(D8-4-Pad6)") (class "Default")
      (node (ref "D8") (pin "6") (pinfunction "4_6") (pintype "passive"))
    )
    (net (code "43") (name "unconnected-(U1-ADC1_2{slash}RTC3{slash}IO3-Pad15)") (class "Default")
      (node (ref "U1") (pin "15") (pinfunction "ADC1_2/RTC3/IO3_15") (pintype "bidirectional"))
    )
    (net (code "44") (name "unconnected-(U1-ADC1_3{slash}RTC4{slash}IO4-Pad4)") (class "Default")
      (node (ref "U1") (pin "4") (pinfunction "ADC1_3/RTC4/IO4_4") (pintype "bidirectional"))
    )
    (net (code "45") (name "unconnected-(U1-ADC1_4{slash}RTC5{slash}IO5-Pad5)") (class "Default")
      (node (ref "U1") (pin "5") (pinfunction "ADC1_4/RTC5/IO5_5") (pintype "bidirectional"))
    )
    (net (code "46") (name "unconnected-(U1-ADC1_5{slash}RTC6{slash}IO6-Pad6)") (class "Default")
      (node (ref "U1") (pin "6") (pinfunction "ADC1_5/RTC6/IO6_6") (pintype "bidirectional"))
    )
    (net (code "47") (name "unconnected-(U1-IO35-Pad28)") (class "Default")
      (node (ref "U1") (pin "28") (pinfunction "IO35_28") (pintype "bidirectional"))
    )
    (net (code "48") (name "unconnected-(U1-IO36-Pad29)") (class "Default")
      (node (ref "U1") (pin "29") (pinfunction "IO36_29") (pintype "bidirectional"))
    )
    (net (code "49") (name "unconnected-(U1-IO37-Pad30)") (class "Default")
      (node (ref "U1") (pin "30") (pinfunction "IO37_30") (pintype "bidirectional"))
    )
    (net (code "50") (name "unconnected-(U1-IO45-Pad26)") (class "Default")
      (node (ref "U1") (pin "26") (pinfunction "IO45_26") (pintype "bidirectional"))
    )
    (net (code "51") (name "unconnected-(U1-IO46-Pad16)") (class "Default")
      (node (ref "U1") (pin "16") (pinfunction "IO46_16") (pintype "bidirectional"))
    )
    (net (code "52") (name "unconnected-(U3-P10-Pad10)") (class "Default")
      (node (ref "U3") (pin "10") (pinfunction "P10_10") (pintype "bidirectional"))
    )
    (net (code "53") (name "unconnected-(U3-P11-Pad11)") (class "Default")
      (node (ref "U3") (pin "11") (pinfunction "P11_11") (pintype "bidirectional"))
    )
    (net (code "54") (name "unconnected-(U3-P12-Pad12)") (class "Default")
      (node (ref "U3") (pin "12") (pinfunction "P12_12") (pintype "bidirectional"))
    )
    (net (code "55") (name "unconnected-(U3-P13-Pad13)") (class "Default")
      (node (ref "U3") (pin "13") (pinfunction "P13_13") (pintype "bidirectional"))
    )
    (net (code "56") (name "unconnected-(U3-P14-Pad14)") (class "Default")
      (node (ref "U3") (pin "14") (pinfunction "P14_14") (pintype "bidirectional"))
    )
    (net (code "57") (name "unconnected-(U3-P15-Pad15)") (class "Default")
      (node (ref "U3") (pin "15") (pinfunction "P15_15") (pintype "bidirectional"))
    )
    (net (code "58") (name "unconnected-(U3-P16-Pad16)") (class "Default")
      (node (ref "U3") (pin "16") (pinfunction "P16_16") (pintype "bidirectional"))
    )
    (net (code "59") (name "unconnected-(U3-P17-Pad17)") (class "Default")
      (node (ref "U3") (pin "17") (pinfunction "P17_17") (pintype "bidirectional"))
    )
  )
)
